# Motherboard.net
KiCad netlist of a schematic drawn in EAGLE
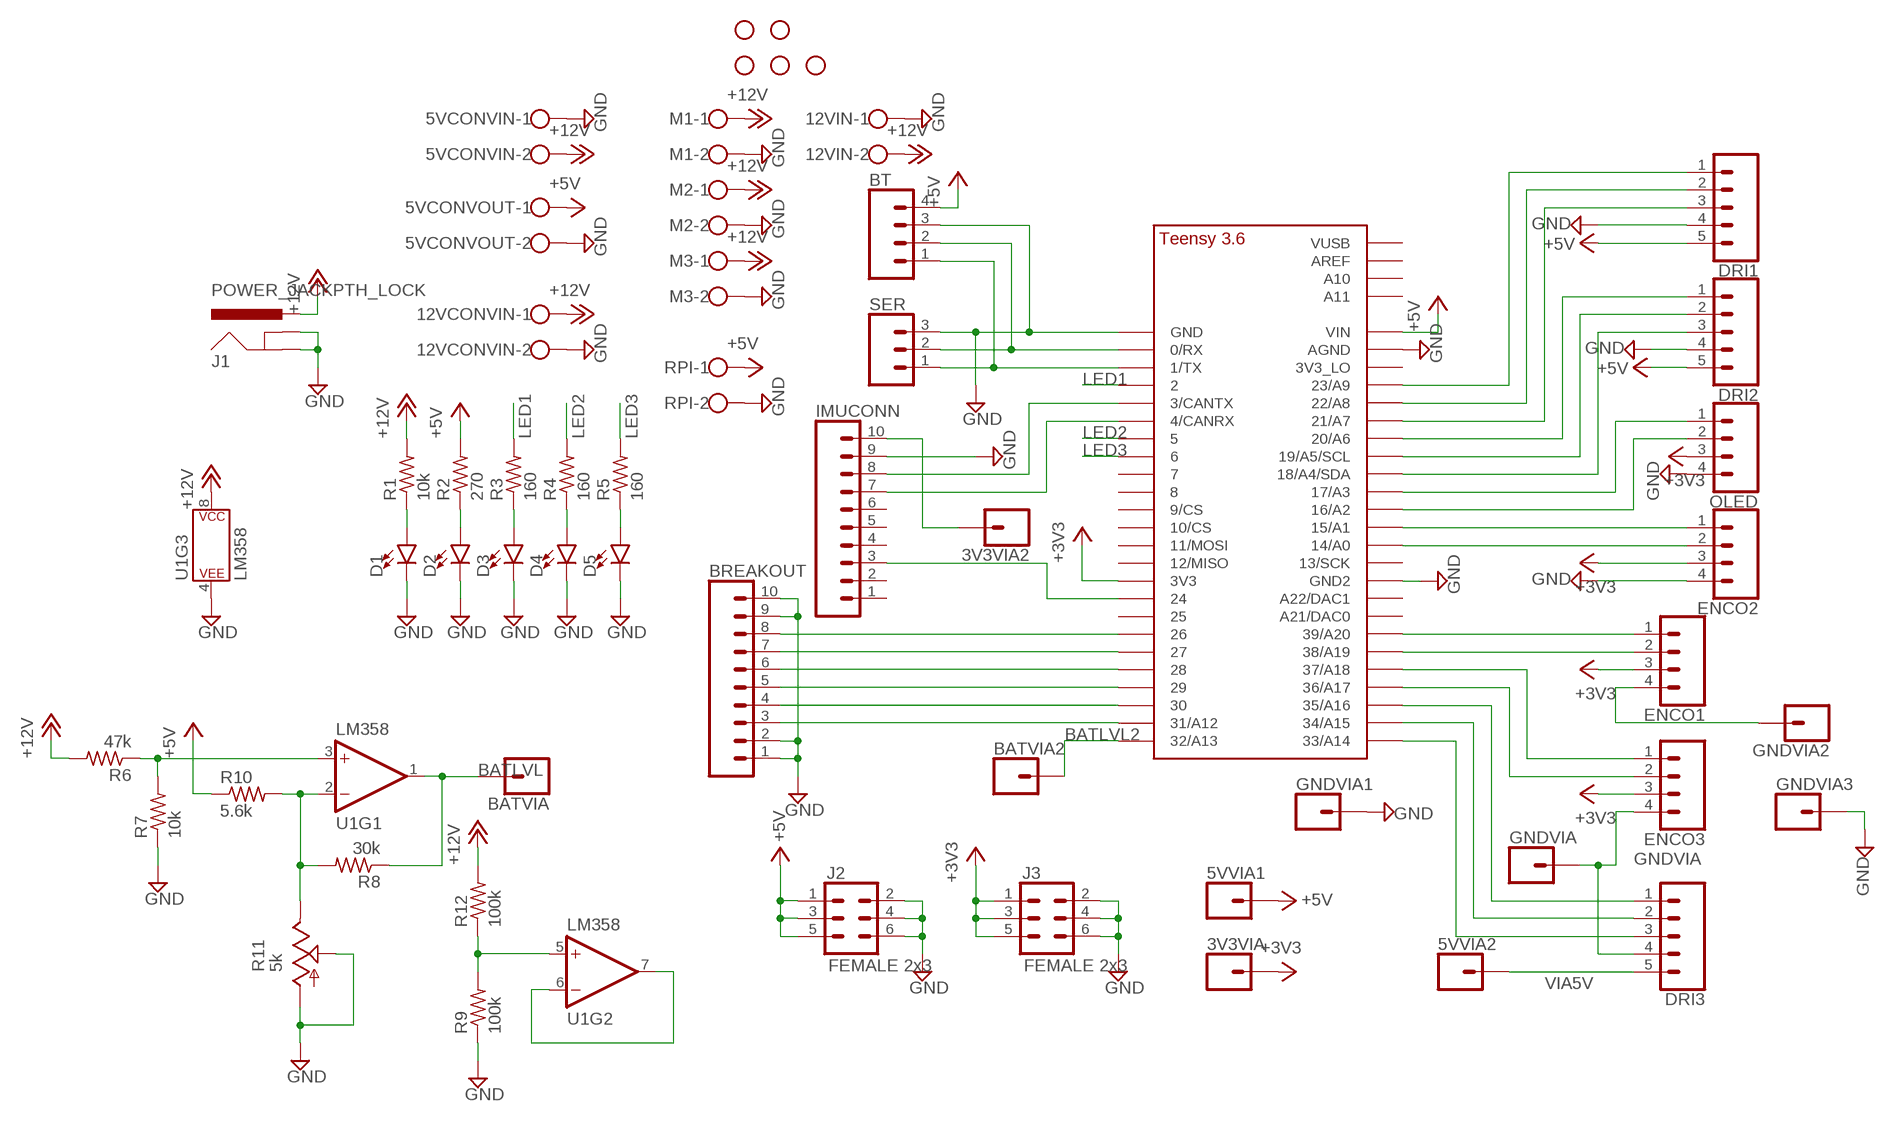
[diagram p0: schematic, sheet 1]

(export (version "E")
  (design (tool "Eeschema 10.0.6"))
  (components
    (comp (ref "3V3VIA")
      (value "CONN_01")
      (footprint "eagle-import:1X01")
      (libsource (lib "eagle-import") (part "CONN_01"))
    )
    (comp (ref "3V3VIA2")
      (value "CONN_01")
      (footprint "eagle-import:1X01")
      (libsource (lib "eagle-import") (part "CONN_01"))
    )
    (comp (ref "5VCONVIN")
      (value "W237-102")
      (footprint "eagle-import:W237-102")
      (fields (field (name "MPN") "237-102"))
      (libsource (lib "eagle-import") (part "W237-102"))
    )
    (comp (ref "5VCONVOUT")
      (value "W237-102")
      (footprint "eagle-import:W237-102")
      (fields (field (name "MPN") "237-102"))
      (libsource (lib "eagle-import") (part "W237-102"))
    )
    (comp (ref "5VVIA1")
      (value "CONN_01")
      (footprint "eagle-import:1X01")
      (libsource (lib "eagle-import") (part "CONN_01"))
    )
    (comp (ref "5VVIA2")
      (value "CONN_01")
      (footprint "eagle-import:1X01")
      (libsource (lib "eagle-import") (part "CONN_01"))
    )
    (comp (ref "12VCONVIN")
      (value "W237-102")
      (footprint "eagle-import:W237-102")
      (fields (field (name "MPN") "237-102"))
      (libsource (lib "eagle-import") (part "W237-102"))
    )
    (comp (ref "12VIN")
      (value "W237-102")
      (footprint "eagle-import:W237-102")
      (fields (field (name "MPN") "237-102"))
      (libsource (lib "eagle-import") (part "W237-102"))
    )
    (comp (ref "BATVIA")
      (value "CONN_01")
      (footprint "eagle-import:1X01")
      (libsource (lib "eagle-import") (part "CONN_01"))
    )
    (comp (ref "BATVIA2")
      (value "CONN_01")
      (footprint "eagle-import:1X01")
      (libsource (lib "eagle-import") (part "CONN_01"))
    )
    (comp (ref "BREAKOUT")
      (value "CONN_10LOCK")
      (footprint "eagle-import:1X10_LOCK")
      (libsource (lib "eagle-import") (part "CONN_10LOCK"))
    )
    (comp (ref "BT")
      (value "CONN_04LOCK")
      (footprint "eagle-import:1X04_LOCK")
      (libsource (lib "eagle-import") (part "CONN_04LOCK"))
    )
    (comp (ref "D1")
      (value "LED5MM-KIT")
      (footprint "eagle-import:LED_5MM-KIT")
      (libsource (lib "eagle-import") (part "LED5MM-KIT"))
    )
    (comp (ref "D2")
      (value "LED5MM-KIT")
      (footprint "eagle-import:LED_5MM-KIT")
      (libsource (lib "eagle-import") (part "LED5MM-KIT"))
    )
    (comp (ref "D3")
      (value "LED5MM-KIT")
      (footprint "eagle-import:LED_5MM-KIT")
      (libsource (lib "eagle-import") (part "LED5MM-KIT"))
    )
    (comp (ref "D4")
      (value "LED5MM-KIT")
      (footprint "eagle-import:LED_5MM-KIT")
      (libsource (lib "eagle-import") (part "LED5MM-KIT"))
    )
    (comp (ref "D5")
      (value "LED5MM-KIT")
      (footprint "eagle-import:LED_5MM-KIT")
      (libsource (lib "eagle-import") (part "LED5MM-KIT"))
    )
    (comp (ref "DRI1")
      (value "CONN_05LOCK")
      (footprint "eagle-import:1X05_LOCK")
      (libsource (lib "eagle-import") (part "CONN_05LOCK"))
    )
    (comp (ref "DRI2")
      (value "CONN_05LOCK")
      (footprint "eagle-import:1X05_LOCK")
      (libsource (lib "eagle-import") (part "CONN_05LOCK"))
    )
    (comp (ref "DRI3")
      (value "CONN_05LOCK")
      (footprint "eagle-import:1X05_LOCK")
      (libsource (lib "eagle-import") (part "CONN_05LOCK"))
    )
    (comp (ref "ENCO1")
      (value "CONN_04LOCK")
      (footprint "eagle-import:1X04_LOCK")
      (libsource (lib "eagle-import") (part "CONN_04LOCK"))
    )
    (comp (ref "ENCO2")
      (value "CONN_04LOCK")
      (footprint "eagle-import:1X04_LOCK")
      (libsource (lib "eagle-import") (part "CONN_04LOCK"))
    )
    (comp (ref "ENCO3")
      (value "CONN_04LOCK")
      (footprint "eagle-import:1X04_LOCK")
      (libsource (lib "eagle-import") (part "CONN_04LOCK"))
    )
    (comp (ref "GNDVIA")
      (value "CONN_01")
      (footprint "eagle-import:1X01")
      (libsource (lib "eagle-import") (part "CONN_01"))
    )
    (comp (ref "GNDVIA1")
      (value "CONN_01")
      (footprint "eagle-import:1X01")
      (libsource (lib "eagle-import") (part "CONN_01"))
    )
    (comp (ref "GNDVIA2")
      (value "CONN_01")
      (footprint "eagle-import:1X01")
      (libsource (lib "eagle-import") (part "CONN_01"))
    )
    (comp (ref "GNDVIA3")
      (value "CONN_01")
      (footprint "eagle-import:1X01")
      (libsource (lib "eagle-import") (part "CONN_01"))
    )
    (comp (ref "H1")
      (value "STAND-OFF")
      (footprint "eagle-import:STAND-OFF")
      (libsource (lib "eagle-import") (part "STAND-OFF"))
    )
    (comp (ref "H2")
      (value "STAND-OFF")
      (footprint "eagle-import:STAND-OFF")
      (libsource (lib "eagle-import") (part "STAND-OFF"))
    )
    (comp (ref "H4")
      (value "STAND-OFF")
      (footprint "eagle-import:STAND-OFF")
      (libsource (lib "eagle-import") (part "STAND-OFF"))
    )
    (comp (ref "H5")
      (value "STAND-OFF")
      (footprint "eagle-import:STAND-OFF")
      (libsource (lib "eagle-import") (part "STAND-OFF"))
    )
    (comp (ref "H6")
      (value "STAND-OFF")
      (footprint "eagle-import:STAND-OFF")
      (libsource (lib "eagle-import") (part "STAND-OFF"))
    )
    (comp (ref "IMUCONN")
      (value "CONN_10LOCK")
      (footprint "eagle-import:1X10_LOCK")
      (libsource (lib "eagle-import") (part "CONN_10LOCK"))
    )
    (comp (ref "J1")
      (value "POWER_JACKPTH_LOCK")
      (footprint "eagle-import:POWER_JACK_PTH_LOCK")
      (libsource (lib "eagle-import") (part "POWER_JACKPTH_LOCK"))
    )
    (comp (ref "J2")
      (value "FEMALE 2x3")
      (footprint "eagle-import:2X3")
      (libsource (lib "eagle-import") (part "CONN_03X2FEMALE"))
    )
    (comp (ref "J3")
      (value "FEMALE 2x3")
      (footprint "eagle-import:2X3")
      (libsource (lib "eagle-import") (part "CONN_03X2FEMALE"))
    )
    (comp (ref "M1")
      (value "W237-102")
      (footprint "eagle-import:W237-102")
      (fields (field (name "MPN") "237-102"))
      (libsource (lib "eagle-import") (part "W237-102"))
    )
    (comp (ref "M2")
      (value "W237-102")
      (footprint "eagle-import:W237-102")
      (fields (field (name "MPN") "237-102"))
      (libsource (lib "eagle-import") (part "W237-102"))
    )
    (comp (ref "M3")
      (value "W237-102")
      (footprint "eagle-import:W237-102")
      (fields (field (name "MPN") "237-102"))
      (libsource (lib "eagle-import") (part "W237-102"))
    )
    (comp (ref "OLED")
      (value "CONN_04LOCK")
      (footprint "eagle-import:1X04_LOCK")
      (libsource (lib "eagle-import") (part "CONN_04LOCK"))
    )
    (comp (ref "R1")
      (value "10k")
      (footprint "eagle-import:0207_10")
      (libsource (lib "eagle-import") (part "R-US_0207/10"))
    )
    (comp (ref "R2")
      (value "270")
      (footprint "eagle-import:0207_10")
      (libsource (lib "eagle-import") (part "R-US_0207/10"))
    )
    (comp (ref "R3")
      (value "160")
      (footprint "eagle-import:0207_10")
      (libsource (lib "eagle-import") (part "R-US_0207/10"))
    )
    (comp (ref "R4")
      (value "160")
      (footprint "eagle-import:0207_10")
      (libsource (lib "eagle-import") (part "R-US_0207/10"))
    )
    (comp (ref "R5")
      (value "160")
      (footprint "eagle-import:0207_10")
      (libsource (lib "eagle-import") (part "R-US_0207/10"))
    )
    (comp (ref "R6")
      (value "47k")
      (footprint "eagle-import:0207_10")
      (libsource (lib "eagle-import") (part "R-US_0207/10"))
    )
    (comp (ref "R7")
      (value "10k")
      (footprint "eagle-import:0207_10")
      (libsource (lib "eagle-import") (part "R-US_0207/10"))
    )
    (comp (ref "R8")
      (value "30k")
      (footprint "eagle-import:0207_10")
      (libsource (lib "eagle-import") (part "R-US_0207/10"))
    )
    (comp (ref "R9")
      (value "100k")
      (footprint "eagle-import:0207_10")
      (libsource (lib "eagle-import") (part "R-US_0207/10"))
    )
    (comp (ref "R10")
      (value "5.6k")
      (footprint "eagle-import:0207_10")
      (libsource (lib "eagle-import") (part "R-US_0207/10"))
    )
    (comp (ref "R11")
      (value "5k")
      (footprint "eagle-import:B25P")
      (libsource (lib "eagle-import") (part "TRIM_US-B25P"))
    )
    (comp (ref "R12")
      (value "100k")
      (footprint "eagle-import:0207_10")
      (libsource (lib "eagle-import") (part "R-US_0207/10"))
    )
    (comp (ref "RPI")
      (value "W237-102")
      (footprint "eagle-import:W237-102")
      (fields (field (name "MPN") "237-102"))
      (libsource (lib "eagle-import") (part "W237-102"))
    )
    (comp (ref "SER")
      (value "CONN_03LOCK")
      (footprint "eagle-import:1X03_LOCK")
      (libsource (lib "eagle-import") (part "CONN_03LOCK"))
    )
    (comp (ref "U$1")
      (value "TEENSY_3.5/3.6_BASIC")
      (footprint "eagle-import:TEENSY_3.5_3.6_BASIC")
      (libsource (lib "eagle-import") (part "TEENSY_3.5/3.6_BASIC"))
    )
    (comp (ref "U1")
      (value "LM358")
      (footprint "eagle-import:DIP08")
      (libsource (lib "eagle-import") (part "LM358"))
    )
  )
  (nets
    (net (code "1") (name "+3V3") (class "Default")
      (node (ref "3V3VIA") (pin "1") (pinfunction "1_1") (pintype "passive"))
      (node (ref "ENCO1") (pin "3") (pinfunction "3_3") (pintype "passive"))
      (node (ref "ENCO2") (pin "3") (pinfunction "3_3") (pintype "passive"))
      (node (ref "ENCO3") (pin "3") (pinfunction "3_3") (pintype "passive"))
      (node (ref "J3") (pin "1") (pinfunction "1_1") (pintype "bidirectional"))
      (node (ref "J3") (pin "3") (pinfunction "3_3") (pintype "bidirectional"))
      (node (ref "J3") (pin "5") (pinfunction "5_5") (pintype "bidirectional"))
      (node (ref "OLED") (pin "3") (pinfunction "3_3") (pintype "passive"))
      (node (ref "U$1") (pin "3V3") (pinfunction "3V3_3V3") (pintype "bidirectional"))
    )
    (net (code "2") (name "+5V") (class "Default")
      (node (ref "5VCONVOUT") (pin "1") (pinfunction "KL_1") (pintype "passive"))
      (node (ref "5VVIA1") (pin "1") (pinfunction "1_1") (pintype "passive"))
      (node (ref "BT") (pin "4") (pinfunction "4_4") (pintype "passive"))
      (node (ref "DRI1") (pin "5") (pinfunction "5_5") (pintype "passive"))
      (node (ref "DRI2") (pin "5") (pinfunction "5_5") (pintype "passive"))
      (node (ref "J2") (pin "1") (pinfunction "1_1") (pintype "bidirectional"))
      (node (ref "J2") (pin "3") (pinfunction "3_3") (pintype "bidirectional"))
      (node (ref "J2") (pin "5") (pinfunction "5_5") (pintype "bidirectional"))
      (node (ref "R10") (pin "1") (pinfunction "1_1") (pintype "passive"))
      (node (ref "R2") (pin "2") (pinfunction "2_2") (pintype "passive"))
      (node (ref "RPI") (pin "1") (pinfunction "KL_1") (pintype "passive"))
      (node (ref "U$1") (pin "VIN") (pinfunction "VIN_VIN") (pintype "bidirectional"))
    )
    (net (code "3") (name "+12V") (class "Default")
      (node (ref "12VCONVIN") (pin "1") (pinfunction "KL_1") (pintype "passive"))
      (node (ref "12VIN") (pin "2") (pinfunction "KL_2") (pintype "passive"))
      (node (ref "5VCONVIN") (pin "2") (pinfunction "KL_2") (pintype "passive"))
      (node (ref "J1") (pin "PWR") (pinfunction "PWR_PWR") (pintype "bidirectional"))
      (node (ref "M1") (pin "1") (pinfunction "KL_1") (pintype "passive"))
      (node (ref "M2") (pin "1") (pinfunction "KL_1") (pintype "passive"))
      (node (ref "M3") (pin "1") (pinfunction "KL_1") (pintype "passive"))
      (node (ref "R1") (pin "2") (pinfunction "2_2") (pintype "passive"))
      (node (ref "R12") (pin "2") (pinfunction "2_2") (pintype "passive"))
      (node (ref "R6") (pin "2") (pinfunction "2_2") (pintype "passive"))
      (node (ref "U1") (pin "8") (pinfunction "P$V+_8") (pintype "bidirectional"))
    )
    (net (code "4") (name "/BATLVL") (class "Default")
      (node (ref "BATVIA") (pin "1") (pinfunction "1_1") (pintype "passive"))
      (node (ref "R8") (pin "1") (pinfunction "1_1") (pintype "passive"))
      (node (ref "U1") (pin "1") (pinfunction "OUT_1") (pintype "output"))
    )
    (net (code "5") (name "/BATLVL2") (class "Default")
      (node (ref "BATVIA2") (pin "1") (pinfunction "1_1") (pintype "passive"))
      (node (ref "U$1") (pin "32/A13") (pinfunction "32/A13_32/A13") (pintype "bidirectional"))
    )
    (net (code "6") (name "/GNDVIA") (class "Default")
      (node (ref "DRI3") (pin "4") (pinfunction "4_4") (pintype "passive"))
      (node (ref "ENCO3") (pin "4") (pinfunction "4_4") (pintype "passive"))
      (node (ref "GNDVIA") (pin "1") (pinfunction "1_1") (pintype "passive"))
    )
    (net (code "7") (name "/LED1") (class "Default")
      (node (ref "R3") (pin "2") (pinfunction "2_2") (pintype "passive"))
      (node (ref "U$1") (pin "2") (pinfunction "2_2") (pintype "bidirectional"))
    )
    (net (code "8") (name "/LED2") (class "Default")
      (node (ref "R4") (pin "2") (pinfunction "2_2") (pintype "passive"))
      (node (ref "U$1") (pin "5") (pinfunction "5_5") (pintype "bidirectional"))
    )
    (net (code "9") (name "/LED3") (class "Default")
      (node (ref "R5") (pin "2") (pinfunction "2_2") (pintype "passive"))
      (node (ref "U$1") (pin "6") (pinfunction "6_6") (pintype "bidirectional"))
    )
    (net (code "10") (name "/VIA5V") (class "Default")
      (node (ref "5VVIA2") (pin "1") (pinfunction "1_1") (pintype "passive"))
      (node (ref "DRI3") (pin "5") (pinfunction "5_5") (pintype "passive"))
    )
    (net (code "11") (name "GND") (class "Default")
      (node (ref "12VCONVIN") (pin "2") (pinfunction "KL_2") (pintype "passive"))
      (node (ref "12VIN") (pin "1") (pinfunction "KL_1") (pintype "passive"))
      (node (ref "5VCONVIN") (pin "1") (pinfunction "KL_1") (pintype "passive"))
      (node (ref "5VCONVOUT") (pin "2") (pinfunction "KL_2") (pintype "passive"))
      (node (ref "BREAKOUT") (pin "1") (pinfunction "1_1") (pintype "passive"))
      (node (ref "BREAKOUT") (pin "10") (pinfunction "10_10") (pintype "passive"))
      (node (ref "BREAKOUT") (pin "2") (pinfunction "2_2") (pintype "passive"))
      (node (ref "BREAKOUT") (pin "9") (pinfunction "9_9") (pintype "passive"))
      (node (ref "BT") (pin "3") (pinfunction "3_3") (pintype "passive"))
      (node (ref "D1") (pin "K") (pinfunction "C_K") (pintype "passive"))
      (node (ref "D2") (pin "K") (pinfunction "C_K") (pintype "passive"))
      (node (ref "D3") (pin "K") (pinfunction "C_K") (pintype "passive"))
      (node (ref "D4") (pin "K") (pinfunction "C_K") (pintype "passive"))
      (node (ref "D5") (pin "K") (pinfunction "C_K") (pintype "passive"))
      (node (ref "DRI1") (pin "4") (pinfunction "4_4") (pintype "passive"))
      (node (ref "DRI2") (pin "4") (pinfunction "4_4") (pintype "passive"))
      (node (ref "ENCO2") (pin "4") (pinfunction "4_4") (pintype "passive"))
      (node (ref "GNDVIA1") (pin "1") (pinfunction "1_1") (pintype "passive"))
      (node (ref "GNDVIA3") (pin "1") (pinfunction "1_1") (pintype "passive"))
      (node (ref "IMUCONN") (pin "9") (pinfunction "9_9") (pintype "passive"))
      (node (ref "J1") (pin "GND") (pinfunction "GND_GND") (pintype "bidirectional"))
      (node (ref "J1") (pin "GNDBREAK") (pinfunction "GNDBREAK_GNDBREAK") (pintype "bidirectional"))
      (node (ref "J2") (pin "2") (pinfunction "2_2") (pintype "bidirectional"))
      (node (ref "J2") (pin "4") (pinfunction "4_4") (pintype "bidirectional"))
      (node (ref "J2") (pin "6") (pinfunction "6_6") (pintype "bidirectional"))
      (node (ref "J3") (pin "2") (pinfunction "2_2") (pintype "bidirectional"))
      (node (ref "J3") (pin "4") (pinfunction "4_4") (pintype "bidirectional"))
      (node (ref "J3") (pin "6") (pinfunction "6_6") (pintype "bidirectional"))
      (node (ref "M1") (pin "2") (pinfunction "KL_2") (pintype "passive"))
      (node (ref "M2") (pin "2") (pinfunction "KL_2") (pintype "passive"))
      (node (ref "M3") (pin "2") (pinfunction "KL_2") (pintype "passive"))
      (node (ref "OLED") (pin "4") (pinfunction "4_4") (pintype "passive"))
      (node (ref "R11") (pin "A") (pinfunction "A_A") (pintype "passive"))
      (node (ref "R11") (pin "S") (pinfunction "S_S") (pintype "passive"))
      (node (ref "R7") (pin "1") (pinfunction "1_1") (pintype "passive"))
      (node (ref "R9") (pin "1") (pinfunction "1_1") (pintype "passive"))
      (node (ref "RPI") (pin "2") (pinfunction "KL_2") (pintype "passive"))
      (node (ref "SER") (pin "3") (pinfunction "3_3") (pintype "passive"))
      (node (ref "U$1") (pin "AGND") (pinfunction "AGND_AGND") (pintype "bidirectional"))
      (node (ref "U$1") (pin "GND") (pinfunction "GND_GND") (pintype "bidirectional"))
      (node (ref "U$1") (pin "GND2") (pinfunction "GND2_GND2") (pintype "bidirectional"))
      (node (ref "U1") (pin "4") (pinfunction "P$V-_4") (pintype "bidirectional"))
    )
    (net (code "12") (name "Net-(3V3VIA2-Pad1)") (class "Default")
      (node (ref "3V3VIA2") (pin "1") (pinfunction "1_1") (pintype "passive"))
      (node (ref "IMUCONN") (pin "10") (pinfunction "10_10") (pintype "passive"))
    )
    (net (code "13") (name "Net-(BREAKOUT-Pad3)") (class "Default")
      (node (ref "BREAKOUT") (pin "3") (pinfunction "3_3") (pintype "passive"))
      (node (ref "U$1") (pin "31/A12") (pinfunction "31/A12_31/A12") (pintype "bidirectional"))
    )
    (net (code "14") (name "Net-(BREAKOUT-Pad4)") (class "Default")
      (node (ref "BREAKOUT") (pin "4") (pinfunction "4_4") (pintype "passive"))
      (node (ref "U$1") (pin "30") (pinfunction "30_30") (pintype "bidirectional"))
    )
    (net (code "15") (name "Net-(BREAKOUT-Pad5)") (class "Default")
      (node (ref "BREAKOUT") (pin "5") (pinfunction "5_5") (pintype "passive"))
      (node (ref "U$1") (pin "29") (pinfunction "29_29") (pintype "bidirectional"))
    )
    (net (code "16") (name "Net-(BREAKOUT-Pad6)") (class "Default")
      (node (ref "BREAKOUT") (pin "6") (pinfunction "6_6") (pintype "passive"))
      (node (ref "U$1") (pin "28") (pinfunction "28_28") (pintype "bidirectional"))
    )
    (net (code "17") (name "Net-(BREAKOUT-Pad7)") (class "Default")
      (node (ref "BREAKOUT") (pin "7") (pinfunction "7_7") (pintype "passive"))
      (node (ref "U$1") (pin "27") (pinfunction "27_27") (pintype "bidirectional"))
    )
    (net (code "18") (name "Net-(BREAKOUT-Pad8)") (class "Default")
      (node (ref "BREAKOUT") (pin "8") (pinfunction "8_8") (pintype "passive"))
      (node (ref "U$1") (pin "26") (pinfunction "26_26") (pintype "bidirectional"))
    )
    (net (code "19") (name "Net-(BT-Pad1)") (class "Default")
      (node (ref "BT") (pin "1") (pinfunction "1_1") (pintype "passive"))
      (node (ref "SER") (pin "1") (pinfunction "1_1") (pintype "passive"))
      (node (ref "U$1") (pin "1/TX") (pinfunction "1/TX_1/TX") (pintype "bidirectional"))
    )
    (net (code "20") (name "Net-(BT-Pad2)") (class "Default")
      (node (ref "BT") (pin "2") (pinfunction "2_2") (pintype "passive"))
      (node (ref "SER") (pin "2") (pinfunction "2_2") (pintype "passive"))
      (node (ref "U$1") (pin "0/RX") (pinfunction "0/RX_0/RX") (pintype "bidirectional"))
    )
    (net (code "21") (name "Net-(D1-PadA)") (class "Default")
      (node (ref "D1") (pin "A") (pinfunction "A_A") (pintype "passive"))
      (node (ref "R1") (pin "1") (pinfunction "1_1") (pintype "passive"))
    )
    (net (code "22") (name "Net-(D2-PadA)") (class "Default")
      (node (ref "D2") (pin "A") (pinfunction "A_A") (pintype "passive"))
      (node (ref "R2") (pin "1") (pinfunction "1_1") (pintype "passive"))
    )
    (net (code "23") (name "Net-(D3-PadA)") (class "Default")
      (node (ref "D3") (pin "A") (pinfunction "A_A") (pintype "passive"))
      (node (ref "R3") (pin "1") (pinfunction "1_1") (pintype "passive"))
    )
    (net (code "24") (name "Net-(D4-PadA)") (class "Default")
      (node (ref "D4") (pin "A") (pinfunction "A_A") (pintype "passive"))
      (node (ref "R4") (pin "1") (pinfunction "1_1") (pintype "passive"))
    )
    (net (code "25") (name "Net-(D5-PadA)") (class "Default")
      (node (ref "D5") (pin "A") (pinfunction "A_A") (pintype "passive"))
      (node (ref "R5") (pin "1") (pinfunction "1_1") (pintype "passive"))
    )
    (net (code "26") (name "Net-(DRI1-Pad1)") (class "Default")
      (node (ref "DRI1") (pin "1") (pinfunction "1_1") (pintype "passive"))
      (node (ref "U$1") (pin "23/A9") (pinfunction "23/A9_23/A9") (pintype "bidirectional"))
    )
    (net (code "27") (name "Net-(DRI1-Pad2)") (class "Default")
      (node (ref "DRI1") (pin "2") (pinfunction "2_2") (pintype "passive"))
      (node (ref "U$1") (pin "22/A8") (pinfunction "22/A8_22/A8") (pintype "bidirectional"))
    )
    (net (code "28") (name "Net-(DRI1-Pad3)") (class "Default")
      (node (ref "DRI1") (pin "3") (pinfunction "3_3") (pintype "passive"))
      (node (ref "U$1") (pin "21/A7") (pinfunction "21/A7_21/A7") (pintype "bidirectional"))
    )
    (net (code "29") (name "Net-(DRI2-Pad1)") (class "Default")
      (node (ref "DRI2") (pin "1") (pinfunction "1_1") (pintype "passive"))
      (node (ref "U$1") (pin "20/A6") (pinfunction "20/A6_20/A6") (pintype "bidirectional"))
    )
    (net (code "30") (name "Net-(DRI2-Pad2)") (class "Default")
      (node (ref "DRI2") (pin "2") (pinfunction "2_2") (pintype "passive"))
      (node (ref "U$1") (pin "19/A5/SCL") (pinfunction "19/A5/SCL_19/A5/SCL") (pintype "bidirectional"))
    )
    (net (code "31") (name "Net-(DRI2-Pad3)") (class "Default")
      (node (ref "DRI2") (pin "3") (pinfunction "3_3") (pintype "passive"))
      (node (ref "U$1") (pin "18/A4/SDA") (pinfunction "18/A4/SDA_18/A4/SDA") (pintype "bidirectional"))
    )
    (net (code "32") (name "Net-(DRI3-Pad1)") (class "Default")
      (node (ref "DRI3") (pin "1") (pinfunction "1_1") (pintype "passive"))
      (node (ref "U$1") (pin "35/A16") (pinfunction "35/A16_35/A16") (pintype "bidirectional"))
    )
    (net (code "33") (name "Net-(DRI3-Pad2)") (class "Default")
      (node (ref "DRI3") (pin "2") (pinfunction "2_2") (pintype "passive"))
      (node (ref "U$1") (pin "34/A15") (pinfunction "34/A15_34/A15") (pintype "bidirectional"))
    )
    (net (code "34") (name "Net-(DRI3-Pad3)") (class "Default")
      (node (ref "DRI3") (pin "3") (pinfunction "3_3") (pintype "passive"))
      (node (ref "U$1") (pin "33/A14") (pinfunction "33/A14_33/A14") (pintype "bidirectional"))
    )
    (net (code "35") (name "Net-(ENCO1-Pad1)") (class "Default")
      (node (ref "ENCO1") (pin "1") (pinfunction "1_1") (pintype "passive"))
      (node (ref "U$1") (pin "39/A20") (pinfunction "39/A20_39/A20") (pintype "bidirectional"))
    )
    (net (code "36") (name "Net-(ENCO1-Pad2)") (class "Default")
      (node (ref "ENCO1") (pin "2") (pinfunction "2_2") (pintype "passive"))
      (node (ref "U$1") (pin "38/A19") (pinfunction "38/A19_38/A19") (pintype "bidirectional"))
    )
    (net (code "37") (name "Net-(ENCO1-Pad4)") (class "Default")
      (node (ref "ENCO1") (pin "4") (pinfunction "4_4") (pintype "passive"))
      (node (ref "GNDVIA2") (pin "1") (pinfunction "1_1") (pintype "passive"))
    )
    (net (code "38") (name "Net-(ENCO2-Pad1)") (class "Default")
      (node (ref "ENCO2") (pin "1") (pinfunction "1_1") (pintype "passive"))
      (node (ref "U$1") (pin "15/A1") (pinfunction "15/A1_15/A1") (pintype "bidirectional"))
    )
    (net (code "39") (name "Net-(ENCO2-Pad2)") (class "Default")
      (node (ref "ENCO2") (pin "2") (pinfunction "2_2") (pintype "passive"))
      (node (ref "U$1") (pin "14/A0") (pinfunction "14/A0_14/A0") (pintype "bidirectional"))
    )
    (net (code "40") (name "Net-(ENCO3-Pad1)") (class "Default")
      (node (ref "ENCO3") (pin "1") (pinfunction "1_1") (pintype "passive"))
      (node (ref "U$1") (pin "37/A18") (pinfunction "37/A18_37/A18") (pintype "bidirectional"))
    )
    (net (code "41") (name "Net-(ENCO3-Pad2)") (class "Default")
      (node (ref "ENCO3") (pin "2") (pinfunction "2_2") (pintype "passive"))
      (node (ref "U$1") (pin "36/A17") (pinfunction "36/A17_36/A17") (pintype "bidirectional"))
    )
    (net (code "42") (name "Net-(IMUCONN-Pad3)") (class "Default")
      (node (ref "IMUCONN") (pin "3") (pinfunction "3_3") (pintype "passive"))
      (node (ref "U$1") (pin "24") (pinfunction "24_24") (pintype "bidirectional"))
    )
    (net (code "43") (name "Net-(IMUCONN-Pad7)") (class "Default")
      (node (ref "IMUCONN") (pin "7") (pinfunction "7_7") (pintype "passive"))
      (node (ref "U$1") (pin "4/CANRX") (pinfunction "4/CANRX_4/CANRX") (pintype "bidirectional"))
    )
    (net (code "44") (name "Net-(IMUCONN-Pad8)") (class "Default")
      (node (ref "IMUCONN") (pin "8") (pinfunction "8_8") (pintype "passive"))
      (node (ref "U$1") (pin "3/CANTX") (pinfunction "3/CANTX_3/CANTX") (pintype "bidirectional"))
    )
    (net (code "45") (name "Net-(OLED-Pad1)") (class "Default")
      (node (ref "OLED") (pin "1") (pinfunction "1_1") (pintype "passive"))
      (node (ref "U$1") (pin "17/A3") (pinfunction "17/A3_17/A3") (pintype "bidirectional"))
    )
    (net (code "46") (name "Net-(OLED-Pad2)") (class "Default")
      (node (ref "OLED") (pin "2") (pinfunction "2_2") (pintype "passive"))
      (node (ref "U$1") (pin "16/A2") (pinfunction "16/A2_16/A2") (pintype "bidirectional"))
    )
    (net (code "47") (name "Net-(U1A-+IN)") (class "Default")
      (node (ref "R6") (pin "1") (pinfunction "1_1") (pintype "passive"))
      (node (ref "R7") (pin "2") (pinfunction "2_2") (pintype "passive"))
      (node (ref "U1") (pin "3") (pinfunction "+IN_3") (pintype "input"))
    )
    (net (code "48") (name "Net-(U1A--IN)") (class "Default")
      (node (ref "R10") (pin "2") (pinfunction "2_2") (pintype "passive"))
      (node (ref "R11") (pin "E") (pinfunction "E_E") (pintype "passive"))
      (node (ref "R8") (pin "2") (pinfunction "2_2") (pintype "passive"))
      (node (ref "U1") (pin "2") (pinfunction "-IN_2") (pintype "input"))
    )
    (net (code "49") (name "Net-(U1B-+IN)") (class "Default")
      (node (ref "R12") (pin "1") (pinfunction "1_1") (pintype "passive"))
      (node (ref "R9") (pin "2") (pinfunction "2_2") (pintype "passive"))
      (node (ref "U1") (pin "5") (pinfunction "+IN_5") (pintype "input"))
    )
    (net (code "50") (name "Net-(U1B--IN)") (class "Default")
      (node (ref "U1") (pin "6") (pinfunction "-IN_6") (pintype "input"))
      (node (ref "U1") (pin "7") (pinfunction "OUT_7") (pintype "output"))
    )
    (net (code "51") (name "unconnected-(IMUCONN-Pad1)") (class "Default")
      (node (ref "IMUCONN") (pin "1") (pinfunction "1_1") (pintype "passive"))
    )
    (net (code "52") (name "unconnected-(IMUCONN-Pad2)") (class "Default")
      (node (ref "IMUCONN") (pin "2") (pinfunction "2_2") (pintype "passive"))
    )
    (net (code "53") (name "unconnected-(IMUCONN-Pad4)") (class "Default")
      (node (ref "IMUCONN") (pin "4") (pinfunction "4_4") (pintype "passive"))
    )
    (net (code "54") (name "unconnected-(IMUCONN-Pad5)") (class "Default")
      (node (ref "IMUCONN") (pin "5") (pinfunction "5_5") (pintype "passive"))
    )
    (net (code "55") (name "unconnected-(IMUCONN-Pad6)") (class "Default")
      (node (ref "IMUCONN") (pin "6") (pinfunction "6_6") (pintype "passive"))
    )
    (net (code "56") (name "unconnected-(U$1-A21{slash}DAC0-Pad21{slash}DAC0)") (class "Default")
      (node (ref "U$1") (pin "21/DAC0") (pinfunction "A21/DAC0_21/DAC0") (pintype "bidirectional"))
    )
    (net (code "57") (name "unconnected-(U$1-Pad3V3_LO)") (class "Default")
      (node (ref "U$1") (pin "3V3_LO") (pinfunction "3V3_LO_3V3_LO") (pintype "bidirectional"))
    )
    (net (code "58") (name "unconnected-(U$1-Pad7)") (class "Default")
      (node (ref "U$1") (pin "7") (pinfunction "7_7") (pintype "bidirectional"))
    )
    (net (code "59") (name "unconnected-(U$1-Pad8)") (class "Default")
      (node (ref "U$1") (pin "8") (pinfunction "8_8") (pintype "bidirectional"))
    )
    (net (code "60") (name "unconnected-(U$1-Pad9{slash}CS)") (class "Default")
      (node (ref "U$1") (pin "9/CS") (pinfunction "9/CS_9/CS") (pintype "bidirectional"))
    )
    (net (code "61") (name "unconnected-(U$1-Pad10{slash}CS)") (class "Default")
      (node (ref "U$1") (pin "10/CS") (pinfunction "10/CS_10/CS") (pintype "bidirectional"))
    )
    (net (code "62") (name "unconnected-(U$1-Pad11{slash}MOSI)") (class "Default")
      (node (ref "U$1") (pin "11/MOSI") (pinfunction "11/MOSI_11/MOSI") (pintype "bidirectional"))
    )
    (net (code "63") (name "unconnected-(U$1-Pad12{slash}MISO)") (class "Default")
      (node (ref "U$1") (pin "12/MISO") (pinfunction "12/MISO_12/MISO") (pintype "bidirectional"))
    )
    (net (code "64") (name "unconnected-(U$1-Pad13{slash}SCK)") (class "Default")
      (node (ref "U$1") (pin "13/SCK") (pinfunction "13/SCK_13/SCK") (pintype "bidirectional"))
    )
    (net (code "65") (name "unconnected-(U$1-Pad25)") (class "Default")
      (node (ref "U$1") (pin "25") (pinfunction "25_25") (pintype "bidirectional"))
    )
    (net (code "66") (name "unconnected-(U$1-PadA10)") (class "Default")
      (node (ref "U$1") (pin "A10") (pinfunction "A10_A10") (pintype "bidirectional"))
    )
    (net (code "67") (name "unconnected-(U$1-PadA11)") (class "Default")
      (node (ref "U$1") (pin "A11") (pinfunction "A11_A11") (pintype "bidirectional"))
    )
    (net (code "68") (name "unconnected-(U$1-PadA22{slash}DAC1)") (class "Default")
      (node (ref "U$1") (pin "A22/DAC1") (pinfunction "A22/DAC1_A22/DAC1") (pintype "bidirectional"))
    )
    (net (code "69") (name "unconnected-(U$1-PadAREF)") (class "Default")
      (node (ref "U$1") (pin "AREF") (pinfunction "AREF_AREF") (pintype "bidirectional"))
    )
    (net (code "70") (name "unconnected-(U$1-PadVUSB)") (class "Default")
      (node (ref "U$1") (pin "VUSB") (pinfunction "VUSB_VUSB") (pintype "bidirectional"))
    )
  )
)
